# CurrentSense.net
KiCad netlist of a schematic drawn in Altium Designer
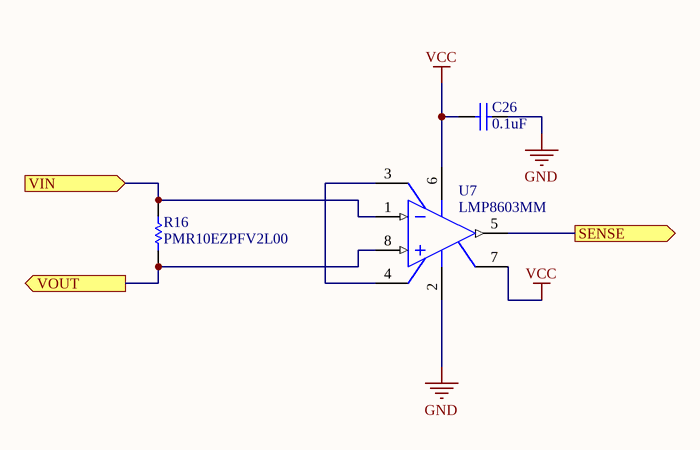
[diagram p0: CurrentSense.SchDoc]

(export (version "E")
  (design (tool "Eeschema 10.0.6"))
  (components
    (comp (ref "C26")
      (value "0.1uF")
      (footprint "CAPC0603(1608)100_L")
      (description "CAP 100nF 100V ±10% 0603 (1608 Metric) Thickness 1mm SMD")
      (fields (field (name "TOLERANCE") "Â±10%"))
      (libsource (lib "Altium Content Vault") (part "CAP"))
    )
    (comp (ref "R16")
      (value "PMR10EZPFV2L00")
      (footprint "0805-SHUNT")
      (libsource (lib "Components") (part "PMR10EZPFV2L00"))
    )
    (comp (ref "U7")
      (value "LMP8603MM")
      (footprint "MUA08A_N")
      (description "60V Common Mode, 100 x Gain, Bidirectional Precision Current Sensing Amplifier, 8-pin Mini SOIC")
      (fields (field (name "MANUFACTURER") "National Semiconductor"))
      (libsource (lib "Altium Content Vault") (part "AMP-SEN-LMP8601-8"))
    )
  )
  (nets
    (net (code "1") (name "/SENSE") (class "Default")
      (node (ref "U7") (pin "5") (pinfunction "OUT_5") (pintype "output"))
    )
    (net (code "2") (name "/VIN") (class "Default")
      (node (ref "R16") (pin "2") (pinfunction "2_2") (pintype "passive"))
      (node (ref "U7") (pin "1") (pinfunction "IN-_1") (pintype "input"))
    )
    (net (code "3") (name "/VOUT") (class "Default")
      (node (ref "R16") (pin "1") (pinfunction "1_1") (pintype "passive"))
      (node (ref "U7") (pin "8") (pinfunction "IN+_8") (pintype "input"))
    )
    (net (code "4") (name "GND") (class "Default")
      (node (ref "C26") (pin "2") (pinfunction "2_2") (pintype "passive"))
      (node (ref "U7") (pin "2") (pinfunction "GND_2") (pintype "power_in"))
    )
    (net (code "5") (name "Net-(U7-A1)") (class "Default")
      (node (ref "U7") (pin "3") (pinfunction "A1_3") (pintype "passive"))
      (node (ref "U7") (pin "4") (pinfunction "A2_4") (pintype "passive"))
    )
    (net (code "6") (name "VCC") (class "Default")
      (node (ref "C26") (pin "1") (pinfunction "1_1") (pintype "passive"))
      (node (ref "U7") (pin "6") (pinfunction "VS_6") (pintype "power_in"))
      (node (ref "U7") (pin "7") (pinfunction "OFS_7") (pintype "passive"))
    )
  )
)
